# board.net
KiCad netlist of a schematic drawn in EAGLE
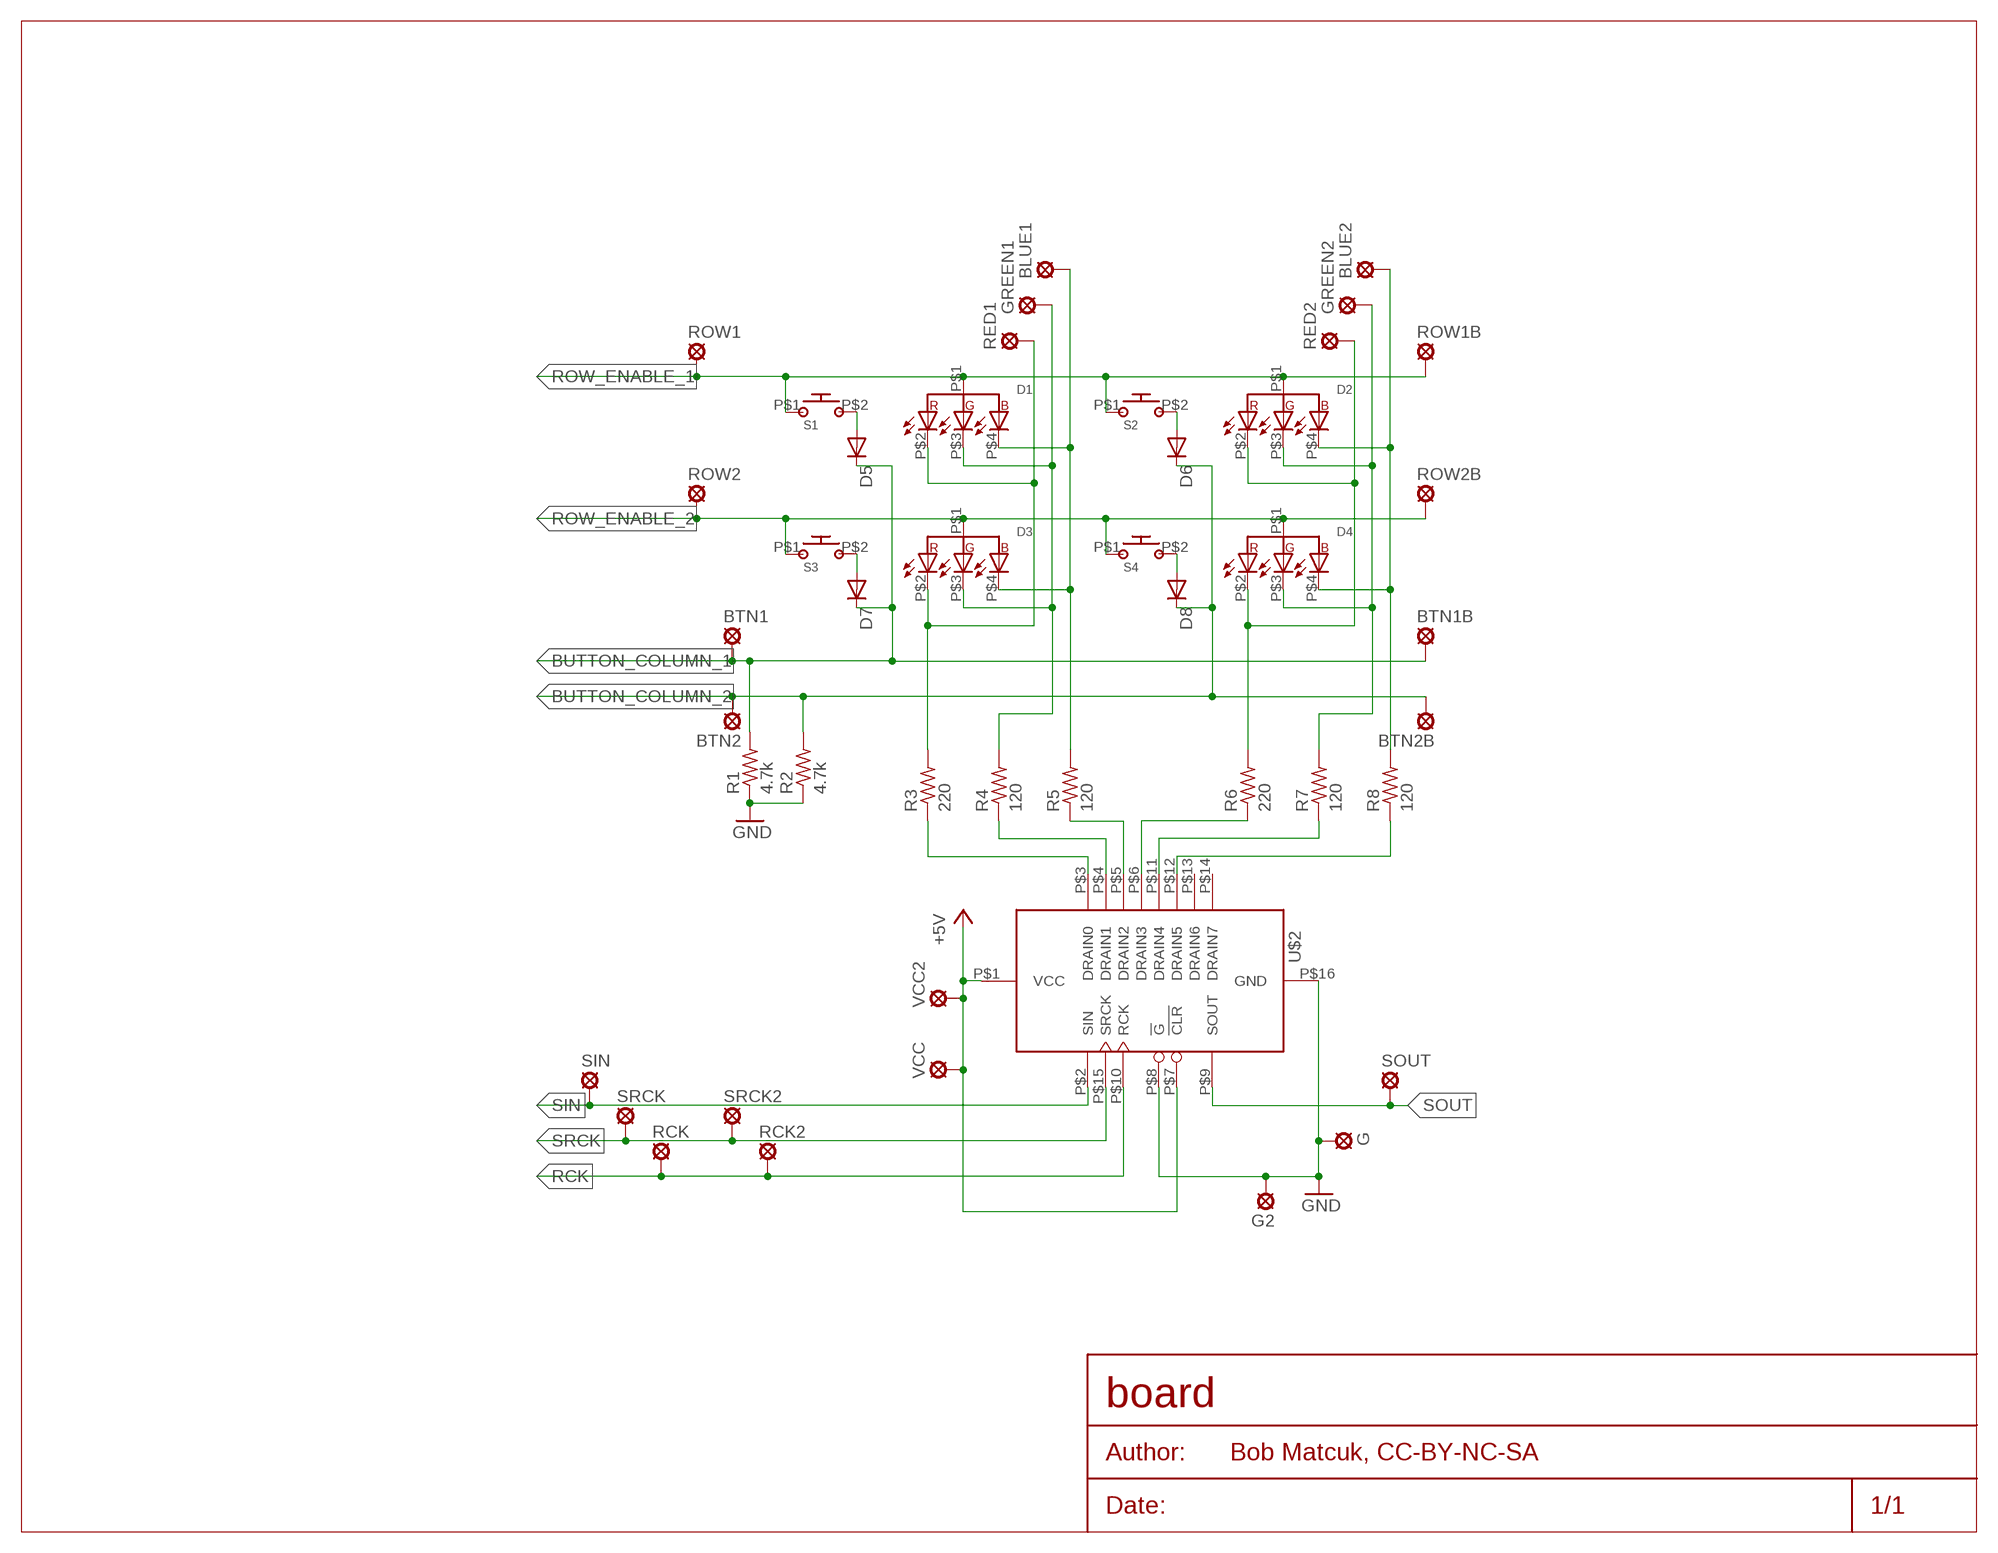
[diagram p0: schematic, sheet 1]

(export (version "E")
  (design (tool "Eeschema 10.0.6"))
  (components
    (comp (ref "BLUE1")
      (value "MCS10B")
      (footprint "eagle-import:MCS10B")
      (libsource (lib "eagle-import") (part "MCS10B"))
    )
    (comp (ref "BLUE2")
      (value "MCS10B")
      (footprint "eagle-import:MCS10B")
      (libsource (lib "eagle-import") (part "MCS10B"))
    )
    (comp (ref "BTN1")
      (value "MCS10B")
      (footprint "eagle-import:MCS10B")
      (libsource (lib "eagle-import") (part "MCS10B"))
    )
    (comp (ref "BTN1B")
      (value "MCS10B")
      (footprint "eagle-import:MCS10B")
      (libsource (lib "eagle-import") (part "MCS10B"))
    )
    (comp (ref "BTN2")
      (value "MCS10B")
      (footprint "eagle-import:MCS10B")
      (libsource (lib "eagle-import") (part "MCS10B"))
    )
    (comp (ref "BTN2B")
      (value "MCS10B")
      (footprint "eagle-import:MCS10B")
      (libsource (lib "eagle-import") (part "MCS10B"))
    )
    (comp (ref "D1")
      (value "FD-5WSRGB-A")
      (footprint "eagle-import:5MM_RGB_LED")
      (libsource (lib "eagle-import") (part "FD-5WSRGB-A"))
    )
    (comp (ref "D2")
      (value "FD-5WSRGB-A")
      (footprint "eagle-import:5MM_RGB_LED")
      (libsource (lib "eagle-import") (part "FD-5WSRGB-A"))
    )
    (comp (ref "D3")
      (value "FD-5WSRGB-A")
      (footprint "eagle-import:5MM_RGB_LED")
      (libsource (lib "eagle-import") (part "FD-5WSRGB-A"))
    )
    (comp (ref "D4")
      (value "FD-5WSRGB-A")
      (footprint "eagle-import:5MM_RGB_LED")
      (libsource (lib "eagle-import") (part "FD-5WSRGB-A"))
    )
    (comp (ref "D5")
      (value "1N4148DO35-7")
      (footprint "eagle-import:DO35-7")
      (libsource (lib "eagle-import") (part "1N4148DO35-7"))
    )
    (comp (ref "D6")
      (value "1N4148DO35-7")
      (footprint "eagle-import:DO35-7")
      (libsource (lib "eagle-import") (part "1N4148DO35-7"))
    )
    (comp (ref "D7")
      (value "1N4148DO35-7")
      (footprint "eagle-import:DO35-7")
      (libsource (lib "eagle-import") (part "1N4148DO35-7"))
    )
    (comp (ref "D8")
      (value "1N4148DO35-7")
      (footprint "eagle-import:DO35-7")
      (libsource (lib "eagle-import") (part "1N4148DO35-7"))
    )
    (comp (ref "G")
      (value "MCS10B")
      (footprint "eagle-import:MCS10B")
      (libsource (lib "eagle-import") (part "MCS10B"))
    )
    (comp (ref "G2")
      (value "MCS10B")
      (footprint "eagle-import:MCS10B")
      (libsource (lib "eagle-import") (part "MCS10B"))
    )
    (comp (ref "GREEN1")
      (value "MCS10B")
      (footprint "eagle-import:MCS10B")
      (libsource (lib "eagle-import") (part "MCS10B"))
    )
    (comp (ref "GREEN2")
      (value "MCS10B")
      (footprint "eagle-import:MCS10B")
      (libsource (lib "eagle-import") (part "MCS10B"))
    )
    (comp (ref "R1")
      (value "4.7k")
      (footprint "eagle-import:0207_10")
      (libsource (lib "eagle-import") (part "R-US_0207/10"))
    )
    (comp (ref "R2")
      (value "4.7k")
      (footprint "eagle-import:0207_10")
      (libsource (lib "eagle-import") (part "R-US_0207/10"))
    )
    (comp (ref "R3")
      (value "220")
      (footprint "eagle-import:0207_7")
      (libsource (lib "eagle-import") (part "R-US_0207/7"))
    )
    (comp (ref "R4")
      (value "120")
      (footprint "eagle-import:0204_5")
      (libsource (lib "eagle-import") (part "R-US_0204/5"))
    )
    (comp (ref "R5")
      (value "120")
      (footprint "eagle-import:0204_5")
      (libsource (lib "eagle-import") (part "R-US_0204/5"))
    )
    (comp (ref "R6")
      (value "220")
      (footprint "eagle-import:0207_7")
      (libsource (lib "eagle-import") (part "R-US_0207/7"))
    )
    (comp (ref "R7")
      (value "120")
      (footprint "eagle-import:0204_5")
      (libsource (lib "eagle-import") (part "R-US_0204/5"))
    )
    (comp (ref "R8")
      (value "120")
      (footprint "eagle-import:0204_5")
      (libsource (lib "eagle-import") (part "R-US_0204/5"))
    )
    (comp (ref "RCK")
      (value "MCS10B")
      (footprint "eagle-import:MCS10B")
      (libsource (lib "eagle-import") (part "MCS10B"))
    )
    (comp (ref "RCK2")
      (value "MCS10B")
      (footprint "eagle-import:MCS10B")
      (libsource (lib "eagle-import") (part "MCS10B"))
    )
    (comp (ref "RED1")
      (value "MCS10B")
      (footprint "eagle-import:MCS10B")
      (libsource (lib "eagle-import") (part "MCS10B"))
    )
    (comp (ref "RED2")
      (value "MCS10B")
      (footprint "eagle-import:MCS10B")
      (libsource (lib "eagle-import") (part "MCS10B"))
    )
    (comp (ref "ROW1")
      (value "MCS10B")
      (footprint "eagle-import:MCS10B")
      (libsource (lib "eagle-import") (part "MCS10B"))
    )
    (comp (ref "ROW1B")
      (value "MCS10B")
      (footprint "eagle-import:MCS10B")
      (libsource (lib "eagle-import") (part "MCS10B"))
    )
    (comp (ref "ROW2")
      (value "MCS10B")
      (footprint "eagle-import:MCS10B")
      (libsource (lib "eagle-import") (part "MCS10B"))
    )
    (comp (ref "ROW2B")
      (value "MCS10B")
      (footprint "eagle-import:MCS10B")
      (libsource (lib "eagle-import") (part "MCS10B"))
    )
    (comp (ref "S1")
      (value "SANWA_OBSC_24_CW")
      (footprint "eagle-import:SANWA_24MM")
      (libsource (lib "eagle-import") (part "SANWA_OBSC_24_CW"))
    )
    (comp (ref "S2")
      (value "SANWA_OBSC_24_CW")
      (footprint "eagle-import:SANWA_24MM")
      (libsource (lib "eagle-import") (part "SANWA_OBSC_24_CW"))
    )
    (comp (ref "S3")
      (value "SANWA_OBSC_24_CW")
      (footprint "eagle-import:SANWA_24MM")
      (libsource (lib "eagle-import") (part "SANWA_OBSC_24_CW"))
    )
    (comp (ref "S4")
      (value "SANWA_OBSC_24_CW")
      (footprint "eagle-import:SANWA_24MM")
      (libsource (lib "eagle-import") (part "SANWA_OBSC_24_CW"))
    )
    (comp (ref "SIN")
      (value "MCS10B")
      (footprint "eagle-import:MCS10B")
      (libsource (lib "eagle-import") (part "MCS10B"))
    )
    (comp (ref "SOUT")
      (value "MCS10B")
      (footprint "eagle-import:MCS10B")
      (libsource (lib "eagle-import") (part "MCS10B"))
    )
    (comp (ref "SRCK")
      (value "MCS10B")
      (footprint "eagle-import:MCS10B")
      (libsource (lib "eagle-import") (part "MCS10B"))
    )
    (comp (ref "SRCK2")
      (value "MCS10B")
      (footprint "eagle-import:MCS10B")
      (libsource (lib "eagle-import") (part "MCS10B"))
    )
    (comp (ref "U$2")
      (value "STPIC6D595")
      (footprint "eagle-import:DIP16")
      (libsource (lib "eagle-import") (part "STPIC6D595"))
    )
    (comp (ref "VCC")
      (value "MCS10B")
      (footprint "eagle-import:MCS10B")
      (libsource (lib "eagle-import") (part "MCS10B"))
    )
    (comp (ref "VCC2")
      (value "MCS10B")
      (footprint "eagle-import:MCS10B")
      (libsource (lib "eagle-import") (part "MCS10B"))
    )
  )
  (nets
    (net (code "1") (name "+5V") (class "Default")
      (node (ref "U$2") (pin "P$1") (pinfunction "VCC_P$1") (pintype "power_in"))
      (node (ref "U$2") (pin "P$7") (pinfunction "~{CLR}_P$7") (pintype "bidirectional"))
      (node (ref "VCC") (pin "MP") (pinfunction "MP_MP") (pintype "passive"))
      (node (ref "VCC2") (pin "MP") (pinfunction "MP_MP") (pintype "passive"))
    )
    (net (code "2") (name "BUTTON_COLUMN_1") (class "Default")
      (node (ref "BTN1") (pin "MP") (pinfunction "MP_MP") (pintype "passive"))
      (node (ref "BTN1B") (pin "MP") (pinfunction "MP_MP") (pintype "passive"))
      (node (ref "D5") (pin "C") (pinfunction "C_C") (pintype "passive"))
      (node (ref "D7") (pin "C") (pinfunction "C_C") (pintype "passive"))
      (node (ref "R1") (pin "2") (pinfunction "2_2") (pintype "passive"))
    )
    (net (code "3") (name "BUTTON_COLUMN_2") (class "Default")
      (node (ref "BTN2") (pin "MP") (pinfunction "MP_MP") (pintype "passive"))
      (node (ref "BTN2B") (pin "MP") (pinfunction "MP_MP") (pintype "passive"))
      (node (ref "D6") (pin "C") (pinfunction "C_C") (pintype "passive"))
      (node (ref "D8") (pin "C") (pinfunction "C_C") (pintype "passive"))
      (node (ref "R2") (pin "2") (pinfunction "2_2") (pintype "passive"))
    )
    (net (code "4") (name "GND") (class "Default")
      (node (ref "G") (pin "MP") (pinfunction "MP_MP") (pintype "passive"))
      (node (ref "G2") (pin "MP") (pinfunction "MP_MP") (pintype "passive"))
      (node (ref "R1") (pin "1") (pinfunction "1_1") (pintype "passive"))
      (node (ref "R2") (pin "1") (pinfunction "1_1") (pintype "passive"))
      (node (ref "U$2") (pin "P$16") (pinfunction "GND_P$16") (pintype "power_in"))
      (node (ref "U$2") (pin "P$8") (pinfunction "~{G}_P$8") (pintype "bidirectional"))
    )
    (net (code "5") (name "Net-(D1-B)") (class "Default")
      (node (ref "BLUE1") (pin "MP") (pinfunction "MP_MP") (pintype "passive"))
      (node (ref "D1") (pin "P$4") (pinfunction "B_P$4") (pintype "passive"))
      (node (ref "D3") (pin "P$4") (pinfunction "B_P$4") (pintype "passive"))
      (node (ref "R5") (pin "2") (pinfunction "2_2") (pintype "passive"))
    )
    (net (code "6") (name "Net-(D1-G)") (class "Default")
      (node (ref "D1") (pin "P$3") (pinfunction "G_P$3") (pintype "passive"))
      (node (ref "D3") (pin "P$3") (pinfunction "G_P$3") (pintype "passive"))
      (node (ref "GREEN1") (pin "MP") (pinfunction "MP_MP") (pintype "passive"))
      (node (ref "R4") (pin "2") (pinfunction "2_2") (pintype "passive"))
    )
    (net (code "7") (name "Net-(D1-R)") (class "Default")
      (node (ref "D1") (pin "P$2") (pinfunction "R_P$2") (pintype "passive"))
      (node (ref "D3") (pin "P$2") (pinfunction "R_P$2") (pintype "passive"))
      (node (ref "R3") (pin "2") (pinfunction "2_2") (pintype "passive"))
      (node (ref "RED1") (pin "MP") (pinfunction "MP_MP") (pintype "passive"))
    )
    (net (code "8") (name "Net-(D2-B)") (class "Default")
      (node (ref "BLUE2") (pin "MP") (pinfunction "MP_MP") (pintype "passive"))
      (node (ref "D2") (pin "P$4") (pinfunction "B_P$4") (pintype "passive"))
      (node (ref "D4") (pin "P$4") (pinfunction "B_P$4") (pintype "passive"))
      (node (ref "R8") (pin "2") (pinfunction "2_2") (pintype "passive"))
    )
    (net (code "9") (name "Net-(D2-G)") (class "Default")
      (node (ref "D2") (pin "P$3") (pinfunction "G_P$3") (pintype "passive"))
      (node (ref "D4") (pin "P$3") (pinfunction "G_P$3") (pintype "passive"))
      (node (ref "GREEN2") (pin "MP") (pinfunction "MP_MP") (pintype "passive"))
      (node (ref "R7") (pin "2") (pinfunction "2_2") (pintype "passive"))
    )
    (net (code "10") (name "Net-(D2-R)") (class "Default")
      (node (ref "D2") (pin "P$2") (pinfunction "R_P$2") (pintype "passive"))
      (node (ref "D4") (pin "P$2") (pinfunction "R_P$2") (pintype "passive"))
      (node (ref "R6") (pin "2") (pinfunction "2_2") (pintype "passive"))
      (node (ref "RED2") (pin "MP") (pinfunction "MP_MP") (pintype "passive"))
    )
    (net (code "11") (name "Net-(D5-PadA)") (class "Default")
      (node (ref "D5") (pin "A") (pinfunction "A_A") (pintype "passive"))
      (node (ref "S1") (pin "P$2") (pinfunction "P$2_P$2") (pintype "passive"))
    )
    (net (code "12") (name "Net-(D6-PadA)") (class "Default")
      (node (ref "D6") (pin "A") (pinfunction "A_A") (pintype "passive"))
      (node (ref "S2") (pin "P$2") (pinfunction "P$2_P$2") (pintype "passive"))
    )
    (net (code "13") (name "Net-(D7-PadA)") (class "Default")
      (node (ref "D7") (pin "A") (pinfunction "A_A") (pintype "passive"))
      (node (ref "S3") (pin "P$2") (pinfunction "P$2_P$2") (pintype "passive"))
    )
    (net (code "14") (name "Net-(D8-PadA)") (class "Default")
      (node (ref "D8") (pin "A") (pinfunction "A_A") (pintype "passive"))
      (node (ref "S4") (pin "P$2") (pinfunction "P$2_P$2") (pintype "passive"))
    )
    (net (code "15") (name "Net-(U$2-DRAIN0)") (class "Default")
      (node (ref "R3") (pin "1") (pinfunction "1_1") (pintype "passive"))
      (node (ref "U$2") (pin "P$3") (pinfunction "DRAIN0_P$3") (pintype "open_collector"))
    )
    (net (code "16") (name "Net-(U$2-DRAIN1)") (class "Default")
      (node (ref "R4") (pin "1") (pinfunction "1_1") (pintype "passive"))
      (node (ref "U$2") (pin "P$4") (pinfunction "DRAIN1_P$4") (pintype "open_collector"))
    )
    (net (code "17") (name "Net-(U$2-DRAIN2)") (class "Default")
      (node (ref "R5") (pin "1") (pinfunction "1_1") (pintype "passive"))
      (node (ref "U$2") (pin "P$5") (pinfunction "DRAIN2_P$5") (pintype "open_collector"))
    )
    (net (code "18") (name "Net-(U$2-DRAIN3)") (class "Default")
      (node (ref "R6") (pin "1") (pinfunction "1_1") (pintype "passive"))
      (node (ref "U$2") (pin "P$6") (pinfunction "DRAIN3_P$6") (pintype "open_collector"))
    )
    (net (code "19") (name "Net-(U$2-DRAIN4)") (class "Default")
      (node (ref "R7") (pin "1") (pinfunction "1_1") (pintype "passive"))
      (node (ref "U$2") (pin "P$11") (pinfunction "DRAIN4_P$11") (pintype "open_collector"))
    )
    (net (code "20") (name "Net-(U$2-DRAIN5)") (class "Default")
      (node (ref "R8") (pin "1") (pinfunction "1_1") (pintype "passive"))
      (node (ref "U$2") (pin "P$12") (pinfunction "DRAIN5_P$12") (pintype "open_collector"))
    )
    (net (code "21") (name "RCK") (class "Default")
      (node (ref "RCK") (pin "MP") (pinfunction "MP_MP") (pintype "passive"))
      (node (ref "RCK2") (pin "MP") (pinfunction "MP_MP") (pintype "passive"))
      (node (ref "U$2") (pin "P$10") (pinfunction "RCK_P$10") (pintype "input"))
    )
    (net (code "22") (name "ROW_ENABLE_1") (class "Default")
      (node (ref "D1") (pin "P$1") (pinfunction "ANODE_P$1") (pintype "passive"))
      (node (ref "D2") (pin "P$1") (pinfunction "ANODE_P$1") (pintype "passive"))
      (node (ref "ROW1") (pin "MP") (pinfunction "MP_MP") (pintype "passive"))
      (node (ref "ROW1B") (pin "MP") (pinfunction "MP_MP") (pintype "passive"))
      (node (ref "S1") (pin "P$1") (pinfunction "P$1_P$1") (pintype "passive"))
      (node (ref "S2") (pin "P$1") (pinfunction "P$1_P$1") (pintype "passive"))
    )
    (net (code "23") (name "ROW_ENABLE_2") (class "Default")
      (node (ref "D3") (pin "P$1") (pinfunction "ANODE_P$1") (pintype "passive"))
      (node (ref "D4") (pin "P$1") (pinfunction "ANODE_P$1") (pintype "passive"))
      (node (ref "ROW2") (pin "MP") (pinfunction "MP_MP") (pintype "passive"))
      (node (ref "ROW2B") (pin "MP") (pinfunction "MP_MP") (pintype "passive"))
      (node (ref "S3") (pin "P$1") (pinfunction "P$1_P$1") (pintype "passive"))
      (node (ref "S4") (pin "P$1") (pinfunction "P$1_P$1") (pintype "passive"))
    )
    (net (code "24") (name "SIN") (class "Default")
      (node (ref "SIN") (pin "MP") (pinfunction "MP_MP") (pintype "passive"))
      (node (ref "U$2") (pin "P$2") (pinfunction "SIN_P$2") (pintype "input"))
    )
    (net (code "25") (name "SOUT") (class "Default")
      (node (ref "SOUT") (pin "MP") (pinfunction "MP_MP") (pintype "passive"))
      (node (ref "U$2") (pin "P$9") (pinfunction "SOUT_P$9") (pintype "output"))
    )
    (net (code "26") (name "SRCK") (class "Default")
      (node (ref "SRCK") (pin "MP") (pinfunction "MP_MP") (pintype "passive"))
      (node (ref "SRCK2") (pin "MP") (pinfunction "MP_MP") (pintype "passive"))
      (node (ref "U$2") (pin "P$15") (pinfunction "SRCK_P$15") (pintype "input"))
    )
    (net (code "27") (name "unconnected-(U$2-DRAIN6-PadP$13)") (class "Default")
      (node (ref "U$2") (pin "P$13") (pinfunction "DRAIN6_P$13") (pintype "open_collector"))
    )
    (net (code "28") (name "unconnected-(U$2-DRAIN7-PadP$14)") (class "Default")
      (node (ref "U$2") (pin "P$14") (pinfunction "DRAIN7_P$14") (pintype "open_collector"))
    )
  )
)
